# PIC32_dev_board.net
KiCad netlist of a schematic drawn in EAGLE
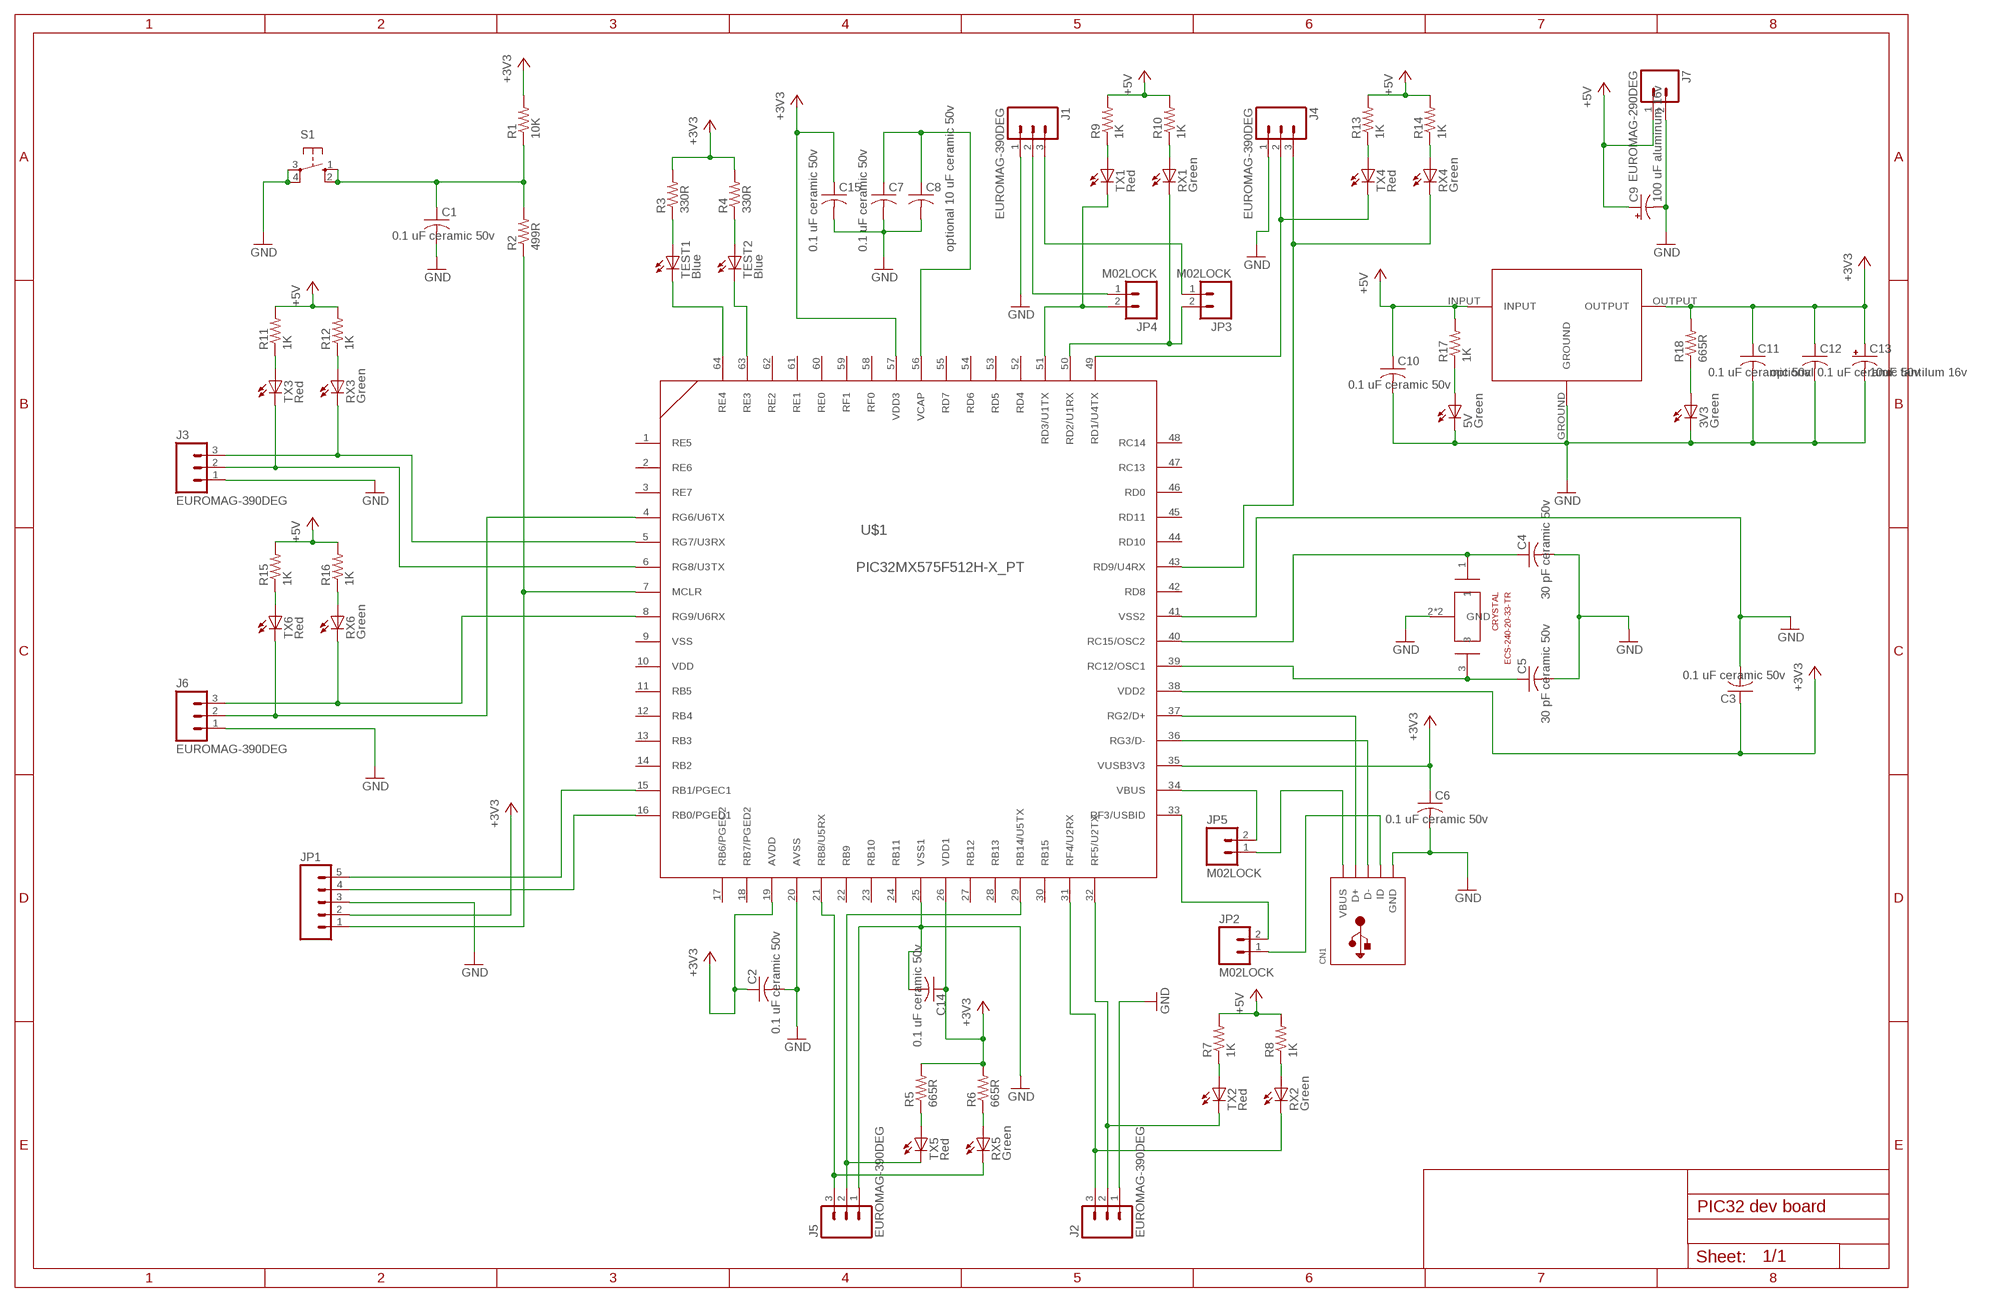
[diagram p0: schematic, sheet 1]

(export (version "E")
  (design (tool "Eeschema 10.0.6"))
  (components
    (comp (ref "3V3")
      (value "Green")
      (footprint "eagle-import:CHIP-LED0805")
      (libsource (lib "eagle-import") (part "LEDCHIP-LED0805"))
    )
    (comp (ref "5V")
      (value "Green")
      (footprint "eagle-import:CHIP-LED0805")
      (libsource (lib "eagle-import") (part "LEDCHIP-LED0805"))
    )
    (comp (ref "C1")
      (value "0.1 uF ceramic 50v")
      (footprint "eagle-import:C0805")
      (libsource (lib "eagle-import") (part "C-USC0805"))
    )
    (comp (ref "C2")
      (value "0.1 uF ceramic 50v")
      (footprint "eagle-import:C0805")
      (libsource (lib "eagle-import") (part "C-USC0805"))
    )
    (comp (ref "C3")
      (value "0.1 uF ceramic 50v")
      (footprint "eagle-import:C0805")
      (libsource (lib "eagle-import") (part "C-USC0805"))
    )
    (comp (ref "C4")
      (value "30 pF ceramic 50v")
      (footprint "eagle-import:C0805")
      (libsource (lib "eagle-import") (part "C-USC0805"))
    )
    (comp (ref "C5")
      (value "30 pF ceramic 50v")
      (footprint "eagle-import:C0805")
      (libsource (lib "eagle-import") (part "C-USC0805"))
    )
    (comp (ref "C6")
      (value "0.1 uF ceramic 50v")
      (footprint "eagle-import:C0805")
      (libsource (lib "eagle-import") (part "C-USC0805"))
    )
    (comp (ref "C7")
      (value "0.1 uF ceramic 50v")
      (footprint "eagle-import:C0805")
      (libsource (lib "eagle-import") (part "C-USC0805"))
    )
    (comp (ref "C8")
      (value "optional 10 uF ceramic 50v")
      (footprint "eagle-import:C0805")
      (libsource (lib "eagle-import") (part "C-USC0805"))
    )
    (comp (ref "C9")
      (value "100 uF aluminum 16v")
      (footprint "eagle-import:153CLV-0605")
      (libsource (lib "eagle-import") (part "CPOL-US153CLV-0605"))
    )
    (comp (ref "C10")
      (value "0.1 uF ceramic 50v")
      (footprint "eagle-import:C0805")
      (libsource (lib "eagle-import") (part "C-USC0805"))
    )
    (comp (ref "C11")
      (value "0.1 uF ceramic 50v")
      (footprint "eagle-import:C0805")
      (libsource (lib "eagle-import") (part "C-USC0805"))
    )
    (comp (ref "C12")
      (value "optional 0.1 uF ceramic 50v")
      (footprint "eagle-import:C0805")
      (libsource (lib "eagle-import") (part "C-USC0805"))
    )
    (comp (ref "C13")
      (value "10uF tantilum 16v")
      (footprint "eagle-import:CT3216")
      (libsource (lib "eagle-import") (part "CPOL-USCT3216"))
    )
    (comp (ref "C14")
      (value "0.1 uF ceramic 50v")
      (footprint "eagle-import:C0805")
      (libsource (lib "eagle-import") (part "C-USC0805"))
    )
    (comp (ref "C15")
      (value "0.1 uF ceramic 50v")
      (footprint "eagle-import:C0805")
      (libsource (lib "eagle-import") (part "C-USC0805"))
    )
    (comp (ref "CN1")
      (value "USBMINIB")
      (footprint "eagle-import:USB-MINIB")
      (libsource (lib "eagle-import") (part "USBMINIB"))
    )
    (comp (ref "ECS-240-20-33-TR")
      (value "CRYSTAL")
      (footprint "eagle-import:ECX-32")
      (libsource (lib "eagle-import") (part "CRYSTAL"))
    )
    (comp (ref "J1")
      (value "EUROMAG-390DEG")
      (footprint "eagle-import:M3")
      (libsource (lib "eagle-import") (part "EUROMAG-390DEG"))
    )
    (comp (ref "J2")
      (value "EUROMAG-390DEG")
      (footprint "eagle-import:M3")
      (libsource (lib "eagle-import") (part "EUROMAG-390DEG"))
    )
    (comp (ref "J3")
      (value "EUROMAG-390DEG")
      (footprint "eagle-import:M3")
      (libsource (lib "eagle-import") (part "EUROMAG-390DEG"))
    )
    (comp (ref "J4")
      (value "EUROMAG-390DEG")
      (footprint "eagle-import:M3")
      (libsource (lib "eagle-import") (part "EUROMAG-390DEG"))
    )
    (comp (ref "J5")
      (value "EUROMAG-390DEG")
      (footprint "eagle-import:M3")
      (libsource (lib "eagle-import") (part "EUROMAG-390DEG"))
    )
    (comp (ref "J6")
      (value "EUROMAG-390DEG")
      (footprint "eagle-import:M3")
      (libsource (lib "eagle-import") (part "EUROMAG-390DEG"))
    )
    (comp (ref "J7")
      (value "EUROMAG-290DEG")
      (footprint "eagle-import:M2")
      (libsource (lib "eagle-import") (part "EUROMAG-290DEG"))
    )
    (comp (ref "JP1")
      (value "M05LOCK")
      (footprint "eagle-import:1X05_LOCK")
      (libsource (lib "eagle-import") (part "M05LOCK"))
    )
    (comp (ref "JP2")
      (value "M02LOCK")
      (footprint "eagle-import:1X02_LOCK")
      (libsource (lib "eagle-import") (part "M02LOCK"))
    )
    (comp (ref "JP3")
      (value "M02LOCK")
      (footprint "eagle-import:1X02_LOCK")
      (libsource (lib "eagle-import") (part "M02LOCK"))
    )
    (comp (ref "JP4")
      (value "M02LOCK")
      (footprint "eagle-import:1X02_LOCK")
      (libsource (lib "eagle-import") (part "M02LOCK"))
    )
    (comp (ref "JP5")
      (value "M02LOCK")
      (footprint "eagle-import:1X02_LOCK")
      (libsource (lib "eagle-import") (part "M02LOCK"))
    )
    (comp (ref "R1")
      (value "10K")
      (footprint "eagle-import:M0805")
      (libsource (lib "eagle-import") (part "R-US_M0805"))
    )
    (comp (ref "R2")
      (value "499R")
      (footprint "eagle-import:M0805")
      (libsource (lib "eagle-import") (part "R-US_M0805"))
    )
    (comp (ref "R3")
      (value "330R")
      (footprint "eagle-import:M0805")
      (libsource (lib "eagle-import") (part "R-US_M0805"))
    )
    (comp (ref "R4")
      (value "330R")
      (footprint "eagle-import:M0805")
      (libsource (lib "eagle-import") (part "R-US_M0805"))
    )
    (comp (ref "R5")
      (value "665R")
      (footprint "eagle-import:M0805")
      (libsource (lib "eagle-import") (part "R-US_M0805"))
    )
    (comp (ref "R6")
      (value "665R")
      (footprint "eagle-import:M0805")
      (libsource (lib "eagle-import") (part "R-US_M0805"))
    )
    (comp (ref "R7")
      (value "1K")
      (footprint "eagle-import:M0805")
      (libsource (lib "eagle-import") (part "R-US_M0805"))
    )
    (comp (ref "R8")
      (value "1K")
      (footprint "eagle-import:M0805")
      (libsource (lib "eagle-import") (part "R-US_M0805"))
    )
    (comp (ref "R9")
      (value "1K")
      (footprint "eagle-import:M0805")
      (libsource (lib "eagle-import") (part "R-US_M0805"))
    )
    (comp (ref "R10")
      (value "1K")
      (footprint "eagle-import:M0805")
      (libsource (lib "eagle-import") (part "R-US_M0805"))
    )
    (comp (ref "R11")
      (value "1K")
      (footprint "eagle-import:M0805")
      (libsource (lib "eagle-import") (part "R-US_M0805"))
    )
    (comp (ref "R12")
      (value "1K")
      (footprint "eagle-import:M0805")
      (libsource (lib "eagle-import") (part "R-US_M0805"))
    )
    (comp (ref "R13")
      (value "1K")
      (footprint "eagle-import:M0805")
      (libsource (lib "eagle-import") (part "R-US_M0805"))
    )
    (comp (ref "R14")
      (value "1K")
      (footprint "eagle-import:M0805")
      (libsource (lib "eagle-import") (part "R-US_M0805"))
    )
    (comp (ref "R15")
      (value "1K")
      (footprint "eagle-import:M0805")
      (libsource (lib "eagle-import") (part "R-US_M0805"))
    )
    (comp (ref "R16")
      (value "1K")
      (footprint "eagle-import:M0805")
      (libsource (lib "eagle-import") (part "R-US_M0805"))
    )
    (comp (ref "R17")
      (value "1K")
      (footprint "eagle-import:M0805")
      (libsource (lib "eagle-import") (part "R-US_M0805"))
    )
    (comp (ref "R18")
      (value "665R")
      (footprint "eagle-import:M0805")
      (libsource (lib "eagle-import") (part "R-US_M0805"))
    )
    (comp (ref "RX1")
      (value "Green")
      (footprint "eagle-import:CHIP-LED0805")
      (libsource (lib "eagle-import") (part "LEDCHIP-LED0805"))
    )
    (comp (ref "RX2")
      (value "Green")
      (footprint "eagle-import:CHIP-LED0805")
      (libsource (lib "eagle-import") (part "LEDCHIP-LED0805"))
    )
    (comp (ref "RX3")
      (value "Green")
      (footprint "eagle-import:CHIP-LED0805")
      (libsource (lib "eagle-import") (part "LEDCHIP-LED0805"))
    )
    (comp (ref "RX4")
      (value "Green")
      (footprint "eagle-import:CHIP-LED0805")
      (libsource (lib "eagle-import") (part "LEDCHIP-LED0805"))
    )
    (comp (ref "RX5")
      (value "Green")
      (footprint "eagle-import:CHIP-LED0805")
      (libsource (lib "eagle-import") (part "LEDCHIP-LED0805"))
    )
    (comp (ref "RX6")
      (value "Green")
      (footprint "eagle-import:CHIP-LED0805")
      (libsource (lib "eagle-import") (part "LEDCHIP-LED0805"))
    )
    (comp (ref "S1")
      (value "10-XX")
      (footprint "eagle-import:B3F-10XX")
      (fields (field (name "MPN") "B3F-1000"))
      (libsource (lib "eagle-import") (part "10-XX"))
    )
    (comp (ref "TEST1")
      (value "Blue")
      (footprint "eagle-import:CHIP-LED0805")
      (libsource (lib "eagle-import") (part "LEDCHIP-LED0805"))
    )
    (comp (ref "TEST2")
      (value "Blue")
      (footprint "eagle-import:CHIP-LED0805")
      (libsource (lib "eagle-import") (part "LEDCHIP-LED0805"))
    )
    (comp (ref "TX1")
      (value "Red")
      (footprint "eagle-import:CHIP-LED0805")
      (libsource (lib "eagle-import") (part "LEDCHIP-LED0805"))
    )
    (comp (ref "TX2")
      (value "Red")
      (footprint "eagle-import:CHIP-LED0805")
      (libsource (lib "eagle-import") (part "LEDCHIP-LED0805"))
    )
    (comp (ref "TX3")
      (value "Red")
      (footprint "eagle-import:CHIP-LED0805")
      (libsource (lib "eagle-import") (part "LEDCHIP-LED0805"))
    )
    (comp (ref "TX4")
      (value "Red")
      (footprint "eagle-import:CHIP-LED0805")
      (libsource (lib "eagle-import") (part "LEDCHIP-LED0805"))
    )
    (comp (ref "TX5")
      (value "Red")
      (footprint "eagle-import:CHIP-LED0805")
      (libsource (lib "eagle-import") (part "LEDCHIP-LED0805"))
    )
    (comp (ref "TX6")
      (value "Red")
      (footprint "eagle-import:CHIP-LED0805")
      (libsource (lib "eagle-import") (part "LEDCHIP-LED0805"))
    )
    (comp (ref "U$1")
      (value "PIC32MX575F512H-X_PT")
      (footprint "eagle-import:TQFP64_10X10MC")
      (libsource (lib "eagle-import") (part "PIC32MX575F512H-X_PT"))
    )
    (comp (ref "U$2")
      (value "LP2950")
      (footprint "eagle-import:TO-252")
      (libsource (lib "eagle-import") (part "LP2950"))
    )
  )
  (nets
    (net (code "1") (name "+3V3") (class "Default")
      (node (ref "C11") (pin "1") (pinfunction "1_1") (pintype "passive"))
      (node (ref "C12") (pin "1") (pinfunction "1_1") (pintype "passive"))
      (node (ref "C13") (pin "+") (pinfunction "+_+") (pintype "passive"))
      (node (ref "C14") (pin "1") (pinfunction "1_1") (pintype "passive"))
      (node (ref "C15") (pin "1") (pinfunction "1_1") (pintype "passive"))
      (node (ref "C2") (pin "1") (pinfunction "1_1") (pintype "passive"))
      (node (ref "C3") (pin "1") (pinfunction "1_1") (pintype "passive"))
      (node (ref "C6") (pin "1") (pinfunction "1_1") (pintype "passive"))
      (node (ref "JP1") (pin "2") (pinfunction "2_2") (pintype "passive"))
      (node (ref "R1") (pin "2") (pinfunction "2_2") (pintype "passive"))
      (node (ref "R18") (pin "2") (pinfunction "2_2") (pintype "passive"))
      (node (ref "R3") (pin "2") (pinfunction "2_2") (pintype "passive"))
      (node (ref "R4") (pin "2") (pinfunction "2_2") (pintype "passive"))
      (node (ref "R5") (pin "2") (pinfunction "2_2") (pintype "passive"))
      (node (ref "R6") (pin "2") (pinfunction "2_2") (pintype "passive"))
      (node (ref "U$1") (pin "19") (pinfunction "AVDD_19") (pintype "bidirectional"))
      (node (ref "U$1") (pin "26") (pinfunction "VDD1_26") (pintype "bidirectional"))
      (node (ref "U$1") (pin "35") (pinfunction "VUSB3V3_35") (pintype "bidirectional"))
      (node (ref "U$1") (pin "38") (pinfunction "VDD2_38") (pintype "bidirectional"))
      (node (ref "U$1") (pin "57") (pinfunction "VDD3_57") (pintype "bidirectional"))
      (node (ref "U$2") (pin "OUTPUT") (pinfunction "OUTPUT_OUTPUT") (pintype "bidirectional"))
    )
    (net (code "2") (name "+5V") (class "Default")
      (node (ref "C10") (pin "1") (pinfunction "1_1") (pintype "passive"))
      (node (ref "C9") (pin "+") (pinfunction "+_+") (pintype "passive"))
      (node (ref "J7") (pin "1") (pinfunction "1_1") (pintype "passive"))
      (node (ref "R10") (pin "2") (pinfunction "2_2") (pintype "passive"))
      (node (ref "R11") (pin "2") (pinfunction "2_2") (pintype "passive"))
      (node (ref "R12") (pin "2") (pinfunction "2_2") (pintype "passive"))
      (node (ref "R13") (pin "2") (pinfunction "2_2") (pintype "passive"))
      (node (ref "R14") (pin "2") (pinfunction "2_2") (pintype "passive"))
      (node (ref "R15") (pin "2") (pinfunction "2_2") (pintype "passive"))
      (node (ref "R16") (pin "2") (pinfunction "2_2") (pintype "passive"))
      (node (ref "R17") (pin "2") (pinfunction "2_2") (pintype "passive"))
      (node (ref "R7") (pin "2") (pinfunction "2_2") (pintype "passive"))
      (node (ref "R8") (pin "2") (pinfunction "2_2") (pintype "passive"))
      (node (ref "R9") (pin "2") (pinfunction "2_2") (pintype "passive"))
      (node (ref "U$2") (pin "INPUT") (pinfunction "INPUT_INPUT") (pintype "bidirectional"))
    )
    (net (code "3") (name "GND") (class "Default")
      (node (ref "3V3") (pin "C") (pinfunction "C_C") (pintype "passive"))
      (node (ref "5V") (pin "C") (pinfunction "C_C") (pintype "passive"))
      (node (ref "C1") (pin "2") (pinfunction "2_2") (pintype "passive"))
      (node (ref "C10") (pin "2") (pinfunction "2_2") (pintype "passive"))
      (node (ref "C11") (pin "2") (pinfunction "2_2") (pintype "passive"))
      (node (ref "C12") (pin "2") (pinfunction "2_2") (pintype "passive"))
      (node (ref "C13") (pin "-") (pinfunction "-_-") (pintype "passive"))
      (node (ref "C14") (pin "2") (pinfunction "2_2") (pintype "passive"))
      (node (ref "C15") (pin "2") (pinfunction "2_2") (pintype "passive"))
      (node (ref "C2") (pin "2") (pinfunction "2_2") (pintype "passive"))
      (node (ref "C3") (pin "2") (pinfunction "2_2") (pintype "passive"))
      (node (ref "C4") (pin "2") (pinfunction "2_2") (pintype "passive"))
      (node (ref "C5") (pin "2") (pinfunction "2_2") (pintype "passive"))
      (node (ref "C6") (pin "2") (pinfunction "2_2") (pintype "passive"))
      (node (ref "C7") (pin "2") (pinfunction "2_2") (pintype "passive"))
      (node (ref "C8") (pin "2") (pinfunction "2_2") (pintype "passive"))
      (node (ref "C9") (pin "-") (pinfunction "-_-") (pintype "passive"))
      (node (ref "CN1") (pin "GND") (pinfunction "GND_GND") (pintype "power_in"))
      (node (ref "ECS-240-20-33-TR") (pin "2") (pinfunction "GND_2") (pintype "bidirectional"))
      (node (ref "ECS-240-20-33-TR") (pin "4") (pinfunction "GND_4") (pintype "bidirectional"))
      (node (ref "J1") (pin "1") (pinfunction "1_1") (pintype "passive"))
      (node (ref "J2") (pin "1") (pinfunction "1_1") (pintype "passive"))
      (node (ref "J3") (pin "1") (pinfunction "1_1") (pintype "passive"))
      (node (ref "J4") (pin "1") (pinfunction "1_1") (pintype "passive"))
      (node (ref "J5") (pin "1") (pinfunction "1_1") (pintype "passive"))
      (node (ref "J6") (pin "1") (pinfunction "1_1") (pintype "passive"))
      (node (ref "J7") (pin "2") (pinfunction "2_2") (pintype "passive"))
      (node (ref "JP1") (pin "3") (pinfunction "3_3") (pintype "passive"))
      (node (ref "S1") (pin "3") (pinfunction "P_3") (pintype "passive"))
      (node (ref "S1") (pin "4") (pinfunction "P1_4") (pintype "passive"))
      (node (ref "U$1") (pin "20") (pinfunction "AVSS_20") (pintype "bidirectional"))
      (node (ref "U$1") (pin "25") (pinfunction "VSS1_25") (pintype "bidirectional"))
      (node (ref "U$1") (pin "41") (pinfunction "VSS2_41") (pintype "bidirectional"))
      (node (ref "U$2") (pin "GROUND") (pinfunction "GROUND_GROUND") (pintype "bidirectional"))
    )
    (net (code "4") (name "Net-(3V3-PadA)") (class "Default")
      (node (ref "3V3") (pin "A") (pinfunction "A_A") (pintype "passive"))
      (node (ref "R18") (pin "1") (pinfunction "1_1") (pintype "passive"))
    )
    (net (code "5") (name "Net-(5V-PadA)") (class "Default")
      (node (ref "5V") (pin "A") (pinfunction "A_A") (pintype "passive"))
      (node (ref "R17") (pin "1") (pinfunction "1_1") (pintype "passive"))
    )
    (net (code "6") (name "Net-(CN1-PadID)") (class "Default")
      (node (ref "CN1") (pin "ID") (pinfunction "ID_ID") (pintype "bidirectional"))
      (node (ref "JP2") (pin "1") (pinfunction "1_1") (pintype "passive"))
    )
    (net (code "7") (name "Net-(CN1-PadVBUS)") (class "Default")
      (node (ref "CN1") (pin "VBUS") (pinfunction "VBUS_VBUS") (pintype "power_in"))
      (node (ref "JP5") (pin "1") (pinfunction "1_1") (pintype "passive"))
    )
    (net (code "8") (name "Net-(J1-Pad2)") (class "Default")
      (node (ref "J1") (pin "2") (pinfunction "2_2") (pintype "passive"))
      (node (ref "JP4") (pin "1") (pinfunction "1_1") (pintype "passive"))
    )
    (net (code "9") (name "Net-(J1-Pad3)") (class "Default")
      (node (ref "J1") (pin "3") (pinfunction "3_3") (pintype "passive"))
      (node (ref "JP3") (pin "1") (pinfunction "1_1") (pintype "passive"))
    )
    (net (code "10") (name "Net-(R3-Pad1)") (class "Default")
      (node (ref "R3") (pin "1") (pinfunction "1_1") (pintype "passive"))
      (node (ref "TEST1") (pin "A") (pinfunction "A_A") (pintype "passive"))
    )
    (net (code "11") (name "Net-(R4-Pad1)") (class "Default")
      (node (ref "R4") (pin "1") (pinfunction "1_1") (pintype "passive"))
      (node (ref "TEST2") (pin "A") (pinfunction "A_A") (pintype "passive"))
    )
    (net (code "12") (name "Net-(R5-Pad1)") (class "Default")
      (node (ref "R5") (pin "1") (pinfunction "1_1") (pintype "passive"))
      (node (ref "TX5") (pin "A") (pinfunction "A_A") (pintype "passive"))
    )
    (net (code "13") (name "Net-(R6-Pad1)") (class "Default")
      (node (ref "R6") (pin "1") (pinfunction "1_1") (pintype "passive"))
      (node (ref "RX5") (pin "A") (pinfunction "A_A") (pintype "passive"))
    )
    (net (code "14") (name "Net-(R7-Pad1)") (class "Default")
      (node (ref "R7") (pin "1") (pinfunction "1_1") (pintype "passive"))
      (node (ref "TX2") (pin "A") (pinfunction "A_A") (pintype "passive"))
    )
    (net (code "15") (name "Net-(R8-Pad1)") (class "Default")
      (node (ref "R8") (pin "1") (pinfunction "1_1") (pintype "passive"))
      (node (ref "RX2") (pin "A") (pinfunction "A_A") (pintype "passive"))
    )
    (net (code "16") (name "Net-(R9-Pad1)") (class "Default")
      (node (ref "R9") (pin "1") (pinfunction "1_1") (pintype "passive"))
      (node (ref "TX1") (pin "A") (pinfunction "A_A") (pintype "passive"))
    )
    (net (code "17") (name "Net-(R10-Pad1)") (class "Default")
      (node (ref "R10") (pin "1") (pinfunction "1_1") (pintype "passive"))
      (node (ref "RX1") (pin "A") (pinfunction "A_A") (pintype "passive"))
    )
    (net (code "18") (name "Net-(R11-Pad1)") (class "Default")
      (node (ref "R11") (pin "1") (pinfunction "1_1") (pintype "passive"))
      (node (ref "TX3") (pin "A") (pinfunction "A_A") (pintype "passive"))
    )
    (net (code "19") (name "Net-(R12-Pad1)") (class "Default")
      (node (ref "R12") (pin "1") (pinfunction "1_1") (pintype "passive"))
      (node (ref "RX3") (pin "A") (pinfunction "A_A") (pintype "passive"))
    )
    (net (code "20") (name "Net-(R13-Pad1)") (class "Default")
      (node (ref "R13") (pin "1") (pinfunction "1_1") (pintype "passive"))
      (node (ref "TX4") (pin "A") (pinfunction "A_A") (pintype "passive"))
    )
    (net (code "21") (name "Net-(R14-Pad1)") (class "Default")
      (node (ref "R14") (pin "1") (pinfunction "1_1") (pintype "passive"))
      (node (ref "RX4") (pin "A") (pinfunction "A_A") (pintype "passive"))
    )
    (net (code "22") (name "Net-(R15-Pad1)") (class "Default")
      (node (ref "R15") (pin "1") (pinfunction "1_1") (pintype "passive"))
      (node (ref "TX6") (pin "A") (pinfunction "A_A") (pintype "passive"))
    )
    (net (code "23") (name "Net-(R16-Pad1)") (class "Default")
      (node (ref "R16") (pin "1") (pinfunction "1_1") (pintype "passive"))
      (node (ref "RX6") (pin "A") (pinfunction "A_A") (pintype "passive"))
    )
    (net (code "24") (name "Net-(S1-S)") (class "Default")
      (node (ref "C1") (pin "1") (pinfunction "1_1") (pintype "passive"))
      (node (ref "R1") (pin "1") (pinfunction "1_1") (pintype "passive"))
      (node (ref "R2") (pin "2") (pinfunction "2_2") (pintype "passive"))
      (node (ref "S1") (pin "1") (pinfunction "S_1") (pintype "passive"))
      (node (ref "S1") (pin "2") (pinfunction "S1_2") (pintype "passive"))
    )
    (net (code "25") (name "Net-(U$1-MCLR)") (class "Default")
      (node (ref "JP1") (pin "1") (pinfunction "1_1") (pintype "passive"))
      (node (ref "R2") (pin "1") (pinfunction "1_1") (pintype "passive"))
      (node (ref "U$1") (pin "7") (pinfunction "MCLR_7") (pintype "bidirectional"))
    )
    (net (code "26") (name "Net-(U$1-RB0{slash}PGED1)") (class "Default")
      (node (ref "JP1") (pin "4") (pinfunction "4_4") (pintype "passive"))
      (node (ref "U$1") (pin "16") (pinfunction "RB0/PGED1_16") (pintype "bidirectional"))
    )
    (net (code "27") (name "Net-(U$1-RB1{slash}PGEC1)") (class "Default")
      (node (ref "JP1") (pin "5") (pinfunction "5_5") (pintype "passive"))
      (node (ref "U$1") (pin "15") (pinfunction "RB1/PGEC1_15") (pintype "bidirectional"))
    )
    (net (code "28") (name "Net-(U$1-RB8{slash}U5RX)") (class "Default")
      (node (ref "J5") (pin "3") (pinfunction "3_3") (pintype "passive"))
      (node (ref "RX5") (pin "C") (pinfunction "C_C") (pintype "passive"))
      (node (ref "U$1") (pin "21") (pinfunction "RB8/U5RX_21") (pintype "bidirectional"))
    )
    (net (code "29") (name "Net-(U$1-RB14{slash}U5TX)") (class "Default")
      (node (ref "J5") (pin "2") (pinfunction "2_2") (pintype "passive"))
      (node (ref "TX5") (pin "C") (pinfunction "C_C") (pintype "passive"))
      (node (ref "U$1") (pin "29") (pinfunction "RB14/U5TX_29") (pintype "bidirectional"))
    )
    (net (code "30") (name "Net-(U$1-RC12{slash}OSC1)") (class "Default")
      (node (ref "C5") (pin "1") (pinfunction "1_1") (pintype "passive"))
      (node (ref "ECS-240-20-33-TR") (pin "3") (pinfunction "3_3") (pintype "bidirectional"))
      (node (ref "U$1") (pin "39") (pinfunction "RC12/OSC1_39") (pintype "bidirectional"))
    )
    (net (code "31") (name "Net-(U$1-RC15{slash}OSC2)") (class "Default")
      (node (ref "C4") (pin "1") (pinfunction "1_1") (pintype "passive"))
      (node (ref "ECS-240-20-33-TR") (pin "1") (pinfunction "1_1") (pintype "bidirectional"))
      (node (ref "U$1") (pin "40") (pinfunction "RC15/OSC2_40") (pintype "bidirectional"))
    )
    (net (code "32") (name "Net-(U$1-RD1{slash}U4TX)") (class "Default")
      (node (ref "J4") (pin "2") (pinfunction "2_2") (pintype "passive"))
      (node (ref "TX4") (pin "C") (pinfunction "C_C") (pintype "passive"))
      (node (ref "U$1") (pin "49") (pinfunction "RD1/U4TX_49") (pintype "bidirectional"))
    )
    (net (code "33") (name "Net-(U$1-RD2{slash}U1RX)") (class "Default")
      (node (ref "JP3") (pin "2") (pinfunction "2_2") (pintype "passive"))
      (node (ref "RX1") (pin "C") (pinfunction "C_C") (pintype "passive"))
      (node (ref "U$1") (pin "50") (pinfunction "RD2/U1RX_50") (pintype "bidirectional"))
    )
    (net (code "34") (name "Net-(U$1-RD3{slash}U1TX)") (class "Default")
      (node (ref "JP4") (pin "2") (pinfunction "2_2") (pintype "passive"))
      (node (ref "TX1") (pin "C") (pinfunction "C_C") (pintype "passive"))
      (node (ref "U$1") (pin "51") (pinfunction "RD3/U1TX_51") (pintype "bidirectional"))
    )
    (net (code "35") (name "Net-(U$1-RD9{slash}U4RX)") (class "Default")
      (node (ref "J4") (pin "3") (pinfunction "3_3") (pintype "passive"))
      (node (ref "RX4") (pin "C") (pinfunction "C_C") (pintype "passive"))
      (node (ref "U$1") (pin "43") (pinfunction "RD9/U4RX_43") (pintype "bidirectional"))
    )
    (net (code "36") (name "Net-(U$1-RE3)") (class "Default")
      (node (ref "TEST2") (pin "C") (pinfunction "C_C") (pintype "passive"))
      (node (ref "U$1") (pin "63") (pinfunction "RE3_63") (pintype "bidirectional"))
    )
    (net (code "37") (name "Net-(U$1-RE4)") (class "Default")
      (node (ref "TEST1") (pin "C") (pinfunction "C_C") (pintype "passive"))
      (node (ref "U$1") (pin "64") (pinfunction "RE4_64") (pintype "bidirectional"))
    )
    (net (code "38") (name "Net-(U$1-RF3{slash}USBID)") (class "Default")
      (node (ref "JP2") (pin "2") (pinfunction "2_2") (pintype "passive"))
      (node (ref "U$1") (pin "33") (pinfunction "RF3/USBID_33") (pintype "bidirectional"))
    )
    (net (code "39") (name "Net-(U$1-RF4{slash}U2RX)") (class "Default")
      (node (ref "J2") (pin "3") (pinfunction "3_3") (pintype "passive"))
      (node (ref "RX2") (pin "C") (pinfunction "C_C") (pintype "passive"))
      (node (ref "U$1") (pin "31") (pinfunction "RF4/U2RX_31") (pintype "bidirectional"))
    )
    (net (code "40") (name "Net-(U$1-RF5{slash}U2TX)") (class "Default")
      (node (ref "J2") (pin "2") (pinfunction "2_2") (pintype "passive"))
      (node (ref "TX2") (pin "C") (pinfunction "C_C") (pintype "passive"))
      (node (ref "U$1") (pin "32") (pinfunction "RF5/U2TX_32") (pintype "bidirectional"))
    )
    (net (code "41") (name "Net-(U$1-RG2{slash}D+)") (class "Default")
      (node (ref "CN1") (pin "D+") (pinfunction "D+_D+") (pintype "bidirectional"))
      (node (ref "U$1") (pin "37") (pinfunction "RG2/D+_37") (pintype "bidirectional"))
    )
    (net (code "42") (name "Net-(U$1-RG3{slash}D-)") (class "Default")
      (node (ref "CN1") (pin "D-") (pinfunction "D-_D-") (pintype "bidirectional"))
      (node (ref "U$1") (pin "36") (pinfunction "RG3/D-_36") (pintype "bidirectional"))
    )
    (net (code "43") (name "Net-(U$1-RG6{slash}U6TX)") (class "Default")
      (node (ref "J6") (pin "2") (pinfunction "2_2") (pintype "passive"))
      (node (ref "TX6") (pin "C") (pinfunction "C_C") (pintype "passive"))
      (node (ref "U$1") (pin "4") (pinfunction "RG6/U6TX_4") (pintype "bidirectional"))
    )
    (net (code "44") (name "Net-(U$1-RG7{slash}U3RX)") (class "Default")
      (node (ref "J3") (pin "3") (pinfunction "3_3") (pintype "passive"))
      (node (ref "RX3") (pin "C") (pinfunction "C_C") (pintype "passive"))
      (node (ref "U$1") (pin "5") (pinfunction "RG7/U3RX_5") (pintype "bidirectional"))
    )
    (net (code "45") (name "Net-(U$1-RG8{slash}U3TX)") (class "Default")
      (node (ref "J3") (pin "2") (pinfunction "2_2") (pintype "passive"))
      (node (ref "TX3") (pin "C") (pinfunction "C_C") (pintype "passive"))
      (node (ref "U$1") (pin "6") (pinfunction "RG8/U3TX_6") (pintype "bidirectional"))
    )
    (net (code "46") (name "Net-(U$1-RG9{slash}U6RX)") (class "Default")
      (node (ref "J6") (pin "3") (pinfunction "3_3") (pintype "passive"))
      (node (ref "RX6") (pin "C") (pinfunction "C_C") (pintype "passive"))
      (node (ref "U$1") (pin "8") (pinfunction "RG9/U6RX_8") (pintype "bidirectional"))
    )
    (net (code "47") (name "Net-(U$1-VBUS)") (class "Default")
      (node (ref "JP5") (pin "2") (pinfunction "2_2") (pintype "passive"))
      (node (ref "U$1") (pin "34") (pinfunction "VBUS_34") (pintype "bidirectional"))
    )
    (net (code "48") (name "Net-(U$1-VCAP)") (class "Default")
      (node (ref "C7") (pin "1") (pinfunction "1_1") (pintype "passive"))
      (node (ref "C8") (pin "1") (pinfunction "1_1") (pintype "passive"))
      (node (ref "U$1") (pin "56") (pinfunction "VCAP_56") (pintype "bidirectional"))
    )
    (net (code "49") (name "unconnected-(U$1-RB2-Pad14)") (class "Default")
      (node (ref "U$1") (pin "14") (pinfunction "RB2_14") (pintype "bidirectional"))
    )
    (net (code "50") (name "unconnected-(U$1-RB3-Pad13)") (class "Default")
      (node (ref "U$1") (pin "13") (pinfunction "RB3_13") (pintype "bidirectional"))
    )
    (net (code "51") (name "unconnected-(U$1-RB4-Pad12)") (class "Default")
      (node (ref "U$1") (pin "12") (pinfunction "RB4_12") (pintype "bidirectional"))
    )
    (net (code "52") (name "unconnected-(U$1-RB5-Pad11)") (class "Default")
      (node (ref "U$1") (pin "11") (pinfunction "RB5_11") (pintype "bidirectional"))
    )
    (net (code "53") (name "unconnected-(U$1-RB6{slash}PGEC2-Pad17)") (class "Default")
      (node (ref "U$1") (pin "17") (pinfunction "RB6/PGEC2_17") (pintype "bidirectional"))
    )
    (net (code "54") (name "unconnected-(U$1-RB7{slash}PGED2-Pad18)") (class "Default")
      (node (ref "U$1") (pin "18") (pinfunction "RB7/PGED2_18") (pintype "bidirectional"))
    )
    (net (code "55") (name "unconnected-(U$1-RB9-Pad22)") (class "Default")
      (node (ref "U$1") (pin "22") (pinfunction "RB9_22") (pintype "bidirectional"))
    )
    (net (code "56") (name "unconnected-(U$1-RB10-Pad23)") (class "Default")
      (node (ref "U$1") (pin "23") (pinfunction "RB10_23") (pintype "bidirectional"))
    )
    (net (code "57") (name "unconnected-(U$1-RB11-Pad24)") (class "Default")
      (node (ref "U$1") (pin "24") (pinfunction "RB11_24") (pintype "bidirectional"))
    )
    (net (code "58") (name "unconnected-(U$1-RB12-Pad27)") (class "Default")
      (node (ref "U$1") (pin "27") (pinfunction "RB12_27") (pintype "bidirectional"))
    )
    (net (code "59") (name "unconnected-(U$1-RB13-Pad28)") (class "Default")
      (node (ref "U$1") (pin "28") (pinfunction "RB13_28") (pintype "bidirectional"))
    )
    (net (code "60") (name "unconnected-(U$1-RB15-Pad30)") (class "Default")
      (node (ref "U$1") (pin "30") (pinfunction "RB15_30") (pintype "bidirectional"))
    )
    (net (code "61") (name "unconnected-(U$1-RC13-Pad47)") (class "Default")
      (node (ref "U$1") (pin "47") (pinfunction "RC13_47") (pintype "bidirectional"))
    )
    (net (code "62") (name "unconnected-(U$1-RC14-Pad48)") (class "Default")
      (node (ref "U$1") (pin "48") (pinfunction "RC14_48") (pintype "bidirectional"))
    )
    (net (code "63") (name "unconnected-(U$1-RD0-Pad46)") (class "Default")
      (node (ref "U$1") (pin "46") (pinfunction "RD0_46") (pintype "bidirectional"))
    )
    (net (code "64") (name "unconnected-(U$1-RD4-Pad52)") (class "Default")
      (node (ref "U$1") (pin "52") (pinfunction "RD4_52") (pintype "bidirectional"))
    )
    (net (code "65") (name "unconnected-(U$1-RD5-Pad53)") (class "Default")
      (node (ref "U$1") (pin "53") (pinfunction "RD5_53") (pintype "bidirectional"))
    )
    (net (code "66") (name "unconnected-(U$1-RD6-Pad54)") (class "Default")
      (node (ref "U$1") (pin "54") (pinfunction "RD6_54") (pintype "bidirectional"))
    )
    (net (code "67") (name "unconnected-(U$1-RD7-Pad55)") (class "Default")
      (node (ref "U$1") (pin "55") (pinfunction "RD7_55") (pintype "bidirectional"))
    )
    (net (code "68") (name "unconnected-(U$1-RD8-Pad42)") (class "Default")
      (node (ref "U$1") (pin "42") (pinfunction "RD8_42") (pintype "bidirectional"))
    )
    (net (code "69") (name "unconnected-(U$1-RD10-Pad44)") (class "Default")
      (node (ref "U$1") (pin "44") (pinfunction "RD10_44") (pintype "bidirectional"))
    )
    (net (code "70") (name "unconnected-(U$1-RD11-Pad45)") (class "Default")
      (node (ref "U$1") (pin "45") (pinfunction "RD11_45") (pintype "bidirectional"))
    )
    (net (code "71") (name "unconnected-(U$1-RE0-Pad60)") (class "Default")
      (node (ref "U$1") (pin "60") (pinfunction "RE0_60") (pintype "bidirectional"))
    )
    (net (code "72") (name "unconnected-(U$1-RE1-Pad61)") (class "Default")
      (node (ref "U$1") (pin "61") (pinfunction "RE1_61") (pintype "bidirectional"))
    )
    (net (code "73") (name "unconnected-(U$1-RE2-Pad62)") (class "Default")
      (node (ref "U$1") (pin "62") (pinfunction "RE2_62") (pintype "bidirectional"))
    )
    (net (code "74") (name "unconnected-(U$1-RE5-Pad1)") (class "Default")
      (node (ref "U$1") (pin "1") (pinfunction "RE5_1") (pintype "bidirectional"))
    )
    (net (code "75") (name "unconnected-(U$1-RE6-Pad2)") (class "Default")
      (node (ref "U$1") (pin "2") (pinfunction "RE6_2") (pintype "bidirectional"))
    )
    (net (code "76") (name "unconnected-(U$1-RE7-Pad3)") (class "Default")
      (node (ref "U$1") (pin "3") (pinfunction "RE7_3") (pintype "bidirectional"))
    )
    (net (code "77") (name "unconnected-(U$1-RF0-Pad58)") (class "Default")
      (node (ref "U$1") (pin "58") (pinfunction "RF0_58") (pintype "bidirectional"))
    )
    (net (code "78") (name "unconnected-(U$1-RF1-Pad59)") (class "Default")
      (node (ref "U$1") (pin "59") (pinfunction "RF1_59") (pintype "bidirectional"))
    )
    (net (code "79") (name "unconnected-(U$1-VDD-Pad10)") (class "Default")
      (node (ref "U$1") (pin "10") (pinfunction "VDD_10") (pintype "bidirectional"))
    )
    (net (code "80") (name "unconnected-(U$1-VSS-Pad9)") (class "Default")
      (node (ref "U$1") (pin "9") (pinfunction "VSS_9") (pintype "bidirectional"))
    )
  )
)
